# T02_noclock_rev3.net
KiCad netlist of a schematic drawn in EAGLE
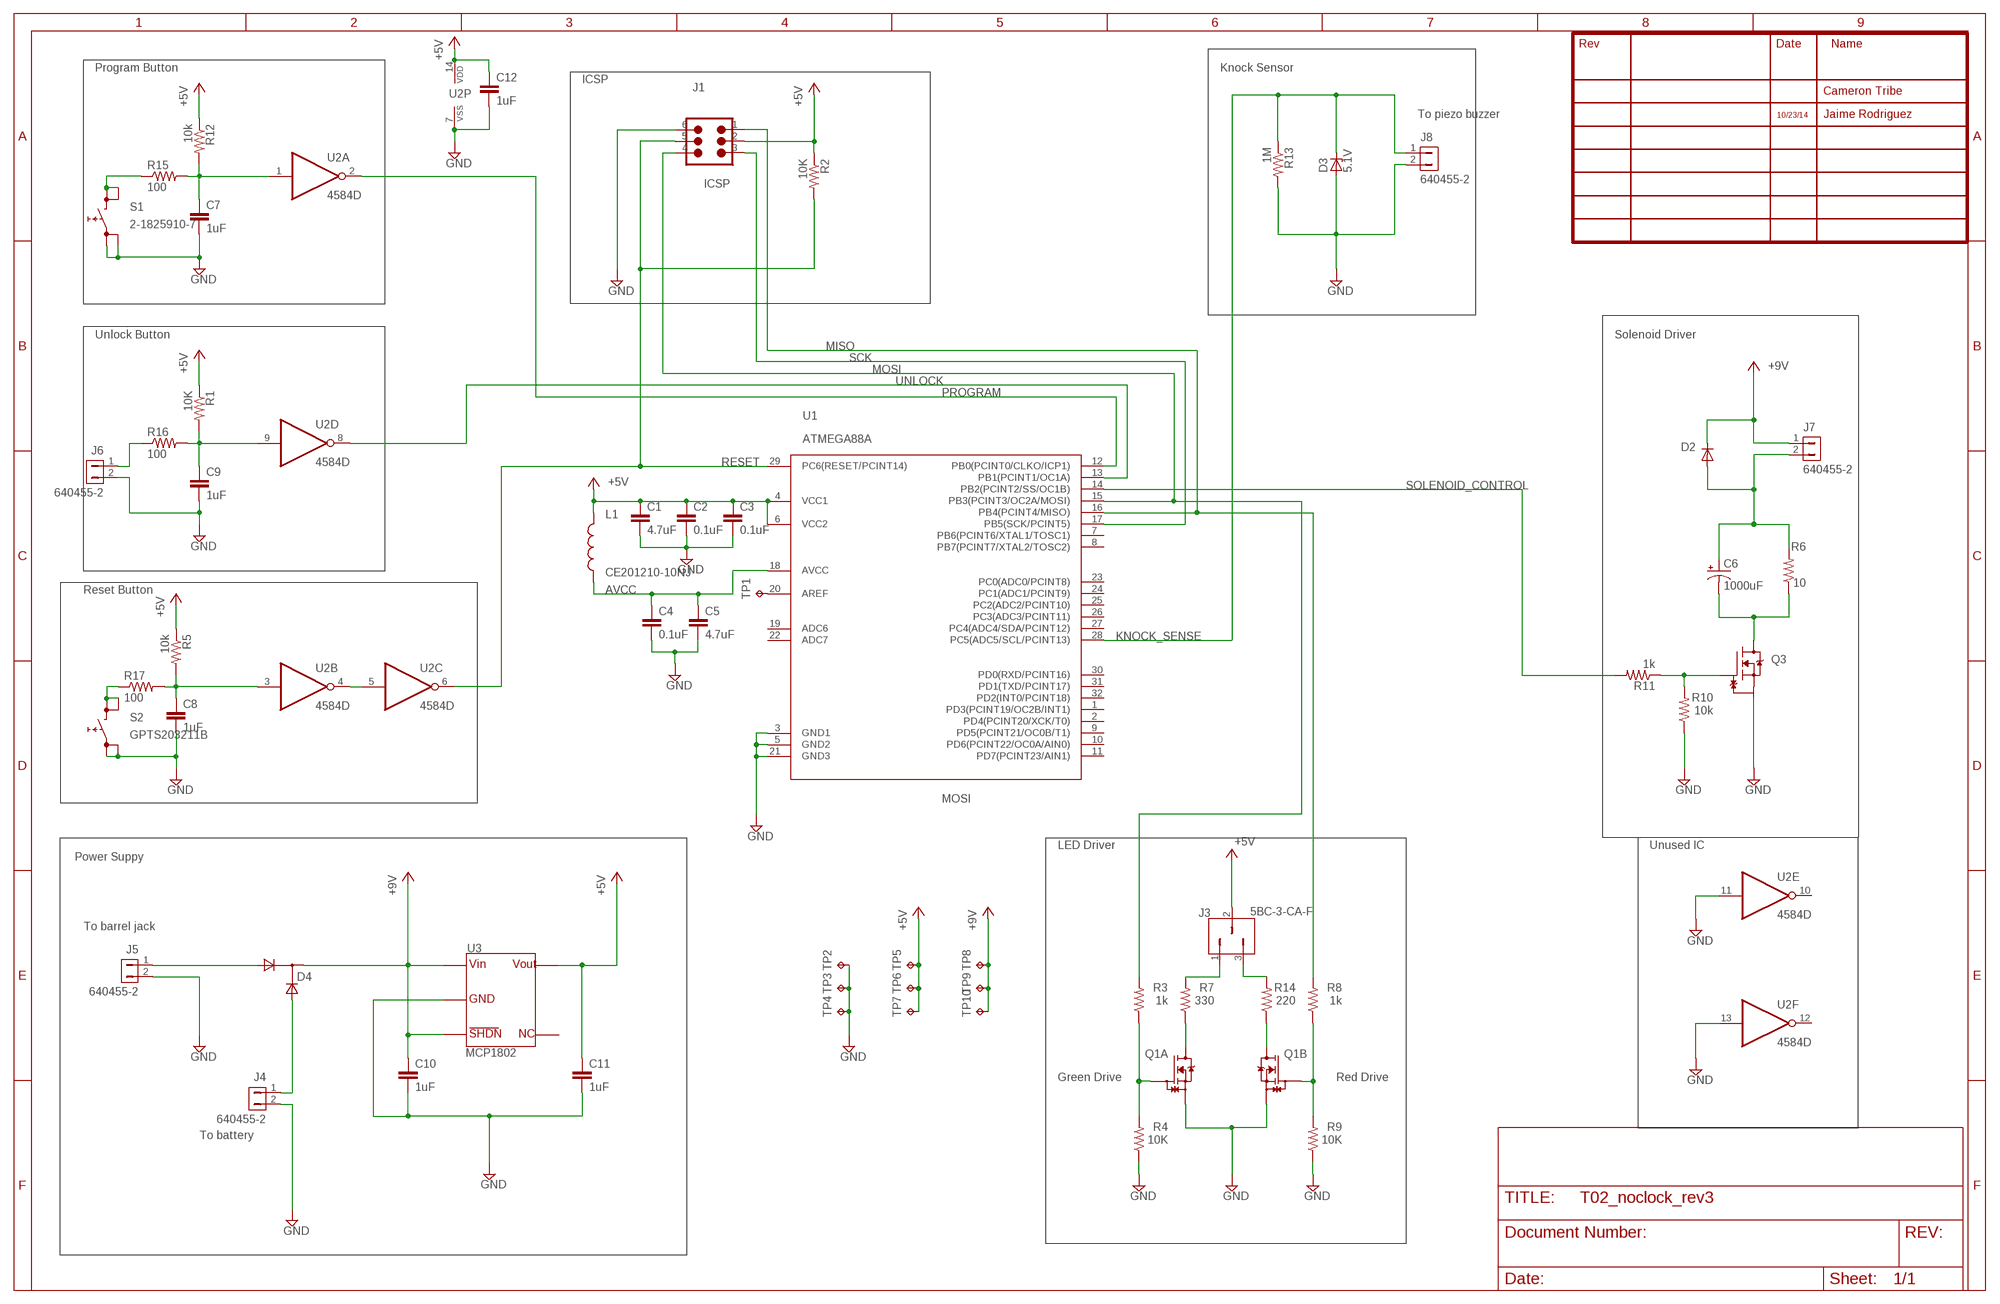
[diagram p0: schematic, sheet 1]

(export (version "E")
  (design (tool "Eeschema 10.0.6"))
  (components
    (comp (ref "C1")
      (value "4.7uF")
      (footprint "eagle-import:C0805")
      (fields (field (name "PARTNUM") "CL21A475KOFNNNE"))
      (libsource (lib "eagle-import") (part "C-EUC0805"))
    )
    (comp (ref "C2")
      (value "0.1uF")
      (footprint "eagle-import:C0805")
      (fields (field (name "PARTNUM") "GRM155R61A104KA01D"))
      (libsource (lib "eagle-import") (part "C-EUC0805"))
    )
    (comp (ref "C3")
      (value "0.1uF")
      (footprint "eagle-import:C0805")
      (fields (field (name "PARTNUM") "GRM155R61A104KA01D"))
      (libsource (lib "eagle-import") (part "C-EUC0805"))
    )
    (comp (ref "C4")
      (value "0.1uF")
      (footprint "eagle-import:C0805")
      (fields (field (name "PARTNUM") "GRM155R61A104KA01D"))
      (libsource (lib "eagle-import") (part "C-EUC0805"))
    )
    (comp (ref "C5")
      (value "4.7uF")
      (footprint "eagle-import:C0805")
      (fields (field (name "PARTNUM") "CL21A475KOFNNNE"))
      (libsource (lib "eagle-import") (part "C-EUC0805"))
    )
    (comp (ref "C6")
      (value "1000uF")
      (footprint "eagle-import:EKY-100ELL102MH20D")
      (libsource (lib "eagle-import") (part "EKY-100ELL102MH20D"))
    )
    (comp (ref "C7")
      (value "1uF")
      (footprint "eagle-import:C0805")
      (fields (field (name "PARTNUM") "CL21B105KBFNNNE"))
      (libsource (lib "eagle-import") (part "C-EUC0805"))
    )
    (comp (ref "C8")
      (value "1uF")
      (footprint "eagle-import:C0805")
      (fields (field (name "PARTNUM") "CL21B105KBFNNNE"))
      (libsource (lib "eagle-import") (part "C-EUC0805"))
    )
    (comp (ref "C9")
      (value "1uF")
      (footprint "eagle-import:C0805")
      (fields (field (name "PARTNUM") "CL21B105KBFNNNE"))
      (libsource (lib "eagle-import") (part "C-EUC0805"))
    )
    (comp (ref "C10")
      (value "1uF")
      (footprint "eagle-import:C0805")
      (fields (field (name "PARTNUM") "CL21B105KBFNNNE"))
      (libsource (lib "eagle-import") (part "C-EUC0805"))
    )
    (comp (ref "C11")
      (value "1uF")
      (footprint "eagle-import:C0805")
      (fields (field (name "PARTNUM") "CL21B105KBFNNNE"))
      (libsource (lib "eagle-import") (part "C-EUC0805"))
    )
    (comp (ref "C12")
      (value "1uF")
      (footprint "eagle-import:C0805")
      (fields (field (name "PARTNUM") "CL21B105KBFNNNE"))
      (libsource (lib "eagle-import") (part "C-EUC0805"))
    )
    (comp (ref "D2")
      (value "GF1")
      (footprint "eagle-import:SMA-DO214AC")
      (fields (field (name "PARTNUM") "S1J"))
      (libsource (lib "eagle-import") (part "GF1"))
    )
    (comp (ref "D3")
      (value "5.1V")
      (footprint "eagle-import:SOT23")
      (fields (field (name "PARTNUM") "BZX84C4V7-TP "))
      (libsource (lib "eagle-import") (part "ZENER-DIODESOT23"))
    )
    (comp (ref "D4")
      (value "PMEG2005CT,215")
      (footprint "eagle-import:SOT-23")
      (libsource (lib "eagle-import") (part "PMEG2005CT,215"))
    )
    (comp (ref "J1")
      (value "ICSP")
      (footprint "eagle-import:ICSP")
      (libsource (lib "eagle-import") (part "ICSP"))
    )
    (comp (ref "J3")
      (value "5BC-3-CA-F")
      (footprint "eagle-import:3_PIN_CONNECTOR")
      (libsource (lib "eagle-import") (part "5BC-3-CA-F"))
    )
    (comp (ref "J4")
      (value "640455-2")
      (footprint "eagle-import:2-PIN_CONNECTOR")
      (libsource (lib "eagle-import") (part "640455-2"))
    )
    (comp (ref "J5")
      (value "640455-2")
      (footprint "eagle-import:2-PIN_CONNECTOR")
      (libsource (lib "eagle-import") (part "640455-2"))
    )
    (comp (ref "J6")
      (value "640455-2")
      (footprint "eagle-import:2-PIN_CONNECTOR")
      (libsource (lib "eagle-import") (part "640455-2"))
    )
    (comp (ref "J7")
      (value "640455-2")
      (footprint "eagle-import:2-PIN_CONNECTOR")
      (libsource (lib "eagle-import") (part "640455-2"))
    )
    (comp (ref "J8")
      (value "640455-2")
      (footprint "eagle-import:2-PIN_CONNECTOR")
      (libsource (lib "eagle-import") (part "640455-2"))
    )
    (comp (ref "L1")
      (value "CE201210-10NJ")
      (footprint "eagle-import:R0805")
      (libsource (lib "eagle-import") (part "CE201210-10NJ"))
    )
    (comp (ref "Q1")
      (value "DMN63D8LDW-7")
      (footprint "eagle-import:SOT363")
      (fields (field (name "PARTNUM") "DMN63D8LDW-7"))
      (libsource (lib "eagle-import") (part "DMN63D8LDW-7"))
    )
    (comp (ref "Q3")
      (value "DMG1012UW-7")
      (footprint "eagle-import:SOT323")
      (libsource (lib "eagle-import") (part "DMG1012UW-7"))
    )
    (comp (ref "R1")
      (value "10K")
      (footprint "eagle-import:R0805")
      (fields (field (name "PARTNUM") "ESR10EZPJ103"))
      (libsource (lib "eagle-import") (part "R-US_R0805"))
    )
    (comp (ref "R2")
      (value "10K")
      (footprint "eagle-import:R0805")
      (fields (field (name "PARTNUM") "ESR10EZPJ103"))
      (libsource (lib "eagle-import") (part "R-US_R0805"))
    )
    (comp (ref "R3")
      (value "1k")
      (footprint "eagle-import:R0805")
      (fields (field (name "PARTNUM") "MCR10ERTF1001"))
      (libsource (lib "eagle-import") (part "R-US_R0805"))
    )
    (comp (ref "R4")
      (value "10K")
      (footprint "eagle-import:R0805")
      (fields (field (name "PARTNUM") "ESR10EZPJ103"))
      (libsource (lib "eagle-import") (part "R-US_R0805"))
    )
    (comp (ref "R5")
      (value "10k")
      (footprint "eagle-import:R0805")
      (fields (field (name "PARTNUM") "ESR10EZPJ103"))
      (libsource (lib "eagle-import") (part "R-US_R0805"))
    )
    (comp (ref "R6")
      (value "10")
      (footprint "eagle-import:R2512")
      (fields (field (name "PARTNUM") "CRM2512-JW-100ELF "))
      (libsource (lib "eagle-import") (part "R-US_R2512"))
    )
    (comp (ref "R7")
      (value "330")
      (footprint "eagle-import:R0805")
      (fields (field (name "PARTNUM") "MCR10ERTF3300"))
      (libsource (lib "eagle-import") (part "R-US_R0805"))
    )
    (comp (ref "R8")
      (value "1k")
      (footprint "eagle-import:R0805")
      (fields (field (name "PARTNUM") "MCR10ERTF1001"))
      (libsource (lib "eagle-import") (part "R-US_R0805"))
    )
    (comp (ref "R9")
      (value "10K")
      (footprint "eagle-import:R0805")
      (fields (field (name "PARTNUM") "ESR10EZPJ103"))
      (libsource (lib "eagle-import") (part "R-US_R0805"))
    )
    (comp (ref "R10")
      (value "10k")
      (footprint "eagle-import:R0805")
      (fields (field (name "PARTNUM") "ESR10EZPJ103"))
      (libsource (lib "eagle-import") (part "R-US_R0805"))
    )
    (comp (ref "R11")
      (value "1k")
      (footprint "eagle-import:R0805")
      (fields (field (name "PARTNUM") "MCR10ERTF1001"))
      (libsource (lib "eagle-import") (part "R-US_R0805"))
    )
    (comp (ref "R12")
      (value "10k")
      (footprint "eagle-import:R0805")
      (fields (field (name "PARTNUM") "ESR10EZPJ103"))
      (libsource (lib "eagle-import") (part "R-US_R0805"))
    )
    (comp (ref "R13")
      (value "1M")
      (footprint "eagle-import:R0805")
      (fields (field (name "PARTNUM") "RMCF0805JT1M00"))
      (libsource (lib "eagle-import") (part "R-US_R0805"))
    )
    (comp (ref "R14")
      (value "220")
      (footprint "eagle-import:R0805")
      (fields (field (name "PARTNUM") "RMCF0805FT220R"))
      (libsource (lib "eagle-import") (part "R-US_R0805"))
    )
    (comp (ref "R15")
      (value "100")
      (footprint "eagle-import:R0805")
      (fields (field (name "PARTNUM") "ESR10EZPJ103"))
      (libsource (lib "eagle-import") (part "R-US_R0805"))
    )
    (comp (ref "R16")
      (value "100")
      (footprint "eagle-import:R0805")
      (fields (field (name "PARTNUM") "ESR10EZPJ103"))
      (libsource (lib "eagle-import") (part "R-US_R0805"))
    )
    (comp (ref "R17")
      (value "100")
      (footprint "eagle-import:R0805")
      (fields (field (name "PARTNUM") "ESR10EZPJ103"))
      (libsource (lib "eagle-import") (part "R-US_R0805"))
    )
    (comp (ref "S1")
      (value "2-1825910-7")
      (footprint "eagle-import:FSM14JH")
      (libsource (lib "eagle-import") (part "2-1825910-7"))
    )
    (comp (ref "S2")
      (value "GPTS203211B")
      (footprint "eagle-import:GPTS203211B")
      (libsource (lib "eagle-import") (part "GPTS203211B"))
    )
    (comp (ref "TP1")
      (value "TPTP19R")
      (footprint "eagle-import:TP19R")
      (libsource (lib "eagle-import") (part "TPTP19R"))
    )
    (comp (ref "TP2")
      (value "TPTP19R")
      (footprint "eagle-import:TP19R")
      (libsource (lib "eagle-import") (part "TPTP19R"))
    )
    (comp (ref "TP3")
      (value "TPTP19R")
      (footprint "eagle-import:TP19R")
      (libsource (lib "eagle-import") (part "TPTP19R"))
    )
    (comp (ref "TP4")
      (value "TPTP19R")
      (footprint "eagle-import:TP19R")
      (libsource (lib "eagle-import") (part "TPTP19R"))
    )
    (comp (ref "TP5")
      (value "TPTP19R")
      (footprint "eagle-import:TP19R")
      (libsource (lib "eagle-import") (part "TPTP19R"))
    )
    (comp (ref "TP6")
      (value "TPTP19R")
      (footprint "eagle-import:TP19R")
      (libsource (lib "eagle-import") (part "TPTP19R"))
    )
    (comp (ref "TP7")
      (value "TPTP19R")
      (footprint "eagle-import:TP19R")
      (libsource (lib "eagle-import") (part "TPTP19R"))
    )
    (comp (ref "TP8")
      (value "TPTP19R")
      (footprint "eagle-import:TP19R")
      (libsource (lib "eagle-import") (part "TPTP19R"))
    )
    (comp (ref "TP9")
      (value "TPTP19R")
      (footprint "eagle-import:TP19R")
      (libsource (lib "eagle-import") (part "TPTP19R"))
    )
    (comp (ref "TP10")
      (value "TPTP19R")
      (footprint "eagle-import:TP19R")
      (libsource (lib "eagle-import") (part "TPTP19R"))
    )
    (comp (ref "U1")
      (value "ATMEGA88A")
      (footprint "eagle-import:TQFP32")
      (fields (field (name "PARTNUM") "ATMEGA88A-AUR "))
      (libsource (lib "eagle-import") (part "ATMEGA88A"))
    )
    (comp (ref "U2")
      (value "4584D")
      (footprint "eagle-import:SO14")
      (fields (field (name "PARTNUM") "4584D"))
      (libsource (lib "eagle-import") (part "4584D"))
    )
    (comp (ref "U3")
      (value "MCP1802")
      (footprint "eagle-import:SOT23-5")
      (libsource (lib "eagle-import") (part "MCP1802"))
    )
  )
  (nets
    (net (code "1") (name "+5V") (class "Default")
      (node (ref "C1") (pin "1") (pinfunction "1_1") (pintype "passive"))
      (node (ref "C11") (pin "1") (pinfunction "1_1") (pintype "passive"))
      (node (ref "C12") (pin "1") (pinfunction "1_1") (pintype "passive"))
      (node (ref "C2") (pin "1") (pinfunction "1_1") (pintype "passive"))
      (node (ref "C3") (pin "1") (pinfunction "1_1") (pintype "passive"))
      (node (ref "J1") (pin "2") (pinfunction "2_2") (pintype "passive"))
      (node (ref "J3") (pin "2") (pinfunction "2_2") (pintype "passive"))
      (node (ref "L1") (pin "2") (pinfunction "2_2") (pintype "passive"))
      (node (ref "R1") (pin "1") (pinfunction "1_1") (pintype "passive"))
      (node (ref "R12") (pin "1") (pinfunction "1_1") (pintype "passive"))
      (node (ref "R2") (pin "1") (pinfunction "1_1") (pintype "passive"))
      (node (ref "R5") (pin "1") (pinfunction "1_1") (pintype "passive"))
      (node (ref "TP5") (pin "TP") (pinfunction "TP_TP") (pintype "input"))
      (node (ref "TP6") (pin "TP") (pinfunction "TP_TP") (pintype "input"))
      (node (ref "TP7") (pin "TP") (pinfunction "TP_TP") (pintype "input"))
      (node (ref "U1") (pin "4") (pinfunction "VCC1_4") (pintype "power_in"))
      (node (ref "U1") (pin "6") (pinfunction "VCC2_6") (pintype "passive"))
      (node (ref "U2") (pin "14") (pinfunction "VDD_14") (pintype "power_in"))
      (node (ref "U3") (pin "5") (pinfunction "VOUT_5") (pintype "passive"))
    )
    (net (code "2") (name "+9V") (class "Default")
      (node (ref "C10") (pin "1") (pinfunction "1_1") (pintype "passive"))
      (node (ref "D2") (pin "K") (pinfunction "C_K") (pintype "passive"))
      (node (ref "D4") (pin "2") (pinfunction "C_2") (pintype "passive"))
      (node (ref "J7") (pin "1") (pinfunction "1_1") (pintype "passive"))
      (node (ref "TP10") (pin "TP") (pinfunction "TP_TP") (pintype "input"))
      (node (ref "TP8") (pin "TP") (pinfunction "TP_TP") (pintype "input"))
      (node (ref "TP9") (pin "TP") (pinfunction "TP_TP") (pintype "input"))
      (node (ref "U3") (pin "1") (pinfunction "VIN_1") (pintype "passive"))
      (node (ref "U3") (pin "3") (pinfunction "SHDN_3") (pintype "passive"))
    )
    (net (code "3") (name "/AVCC") (class "Default")
      (node (ref "C4") (pin "1") (pinfunction "1_1") (pintype "passive"))
      (node (ref "C5") (pin "1") (pinfunction "1_1") (pintype "passive"))
      (node (ref "L1") (pin "1") (pinfunction "1_1") (pintype "passive"))
      (node (ref "U1") (pin "18") (pinfunction "AVCC_18") (pintype "power_in"))
    )
    (net (code "4") (name "/KNOCK_SENSE") (class "Default")
      (node (ref "D3") (pin "3") (pinfunction "C_3") (pintype "passive"))
      (node (ref "J8") (pin "1") (pinfunction "1_1") (pintype "passive"))
      (node (ref "R13") (pin "1") (pinfunction "1_1") (pintype "passive"))
      (node (ref "U1") (pin "28") (pinfunction "PC5(ADC5/SCL/PCINT13)_28") (pintype "bidirectional"))
    )
    (net (code "5") (name "/MISO") (class "Default")
      (node (ref "J1") (pin "1") (pinfunction "1_1") (pintype "passive"))
      (node (ref "R8") (pin "2") (pinfunction "2_2") (pintype "passive"))
      (node (ref "U1") (pin "16") (pinfunction "PB4(PCINT4/MISO)_16") (pintype "bidirectional"))
    )
    (net (code "6") (name "/MOSI") (class "Default")
      (node (ref "J1") (pin "4") (pinfunction "4_4") (pintype "passive"))
      (node (ref "R3") (pin "2") (pinfunction "2_2") (pintype "passive"))
      (node (ref "U1") (pin "15") (pinfunction "PB3(PCINT3/OC2A/MOSI)_15") (pintype "bidirectional"))
    )
    (net (code "7") (name "/PROGRAM") (class "Default")
      (node (ref "U1") (pin "12") (pinfunction "PB0(PCINT0/CLKO/ICP1)_12") (pintype "bidirectional"))
      (node (ref "U2") (pin "2") (pinfunction "O_2") (pintype "output"))
    )
    (net (code "8") (name "/RESET") (class "Default")
      (node (ref "J1") (pin "5") (pinfunction "5_5") (pintype "passive"))
      (node (ref "R2") (pin "2") (pinfunction "2_2") (pintype "passive"))
      (node (ref "U1") (pin "29") (pinfunction "PC6(RESET/PCINT14)_29") (pintype "bidirectional"))
      (node (ref "U2") (pin "6") (pinfunction "O_6") (pintype "output"))
    )
    (net (code "9") (name "/SCK") (class "Default")
      (node (ref "J1") (pin "3") (pinfunction "3_3") (pintype "passive"))
      (node (ref "U1") (pin "17") (pinfunction "PB5(SCK/PCINT5)_17") (pintype "bidirectional"))
    )
    (net (code "10") (name "/SOLENOID_CONTROL") (class "Default")
      (node (ref "R11") (pin "2") (pinfunction "2_2") (pintype "passive"))
      (node (ref "U1") (pin "14") (pinfunction "PB2(PCINT2/SS/OC1B)_14") (pintype "bidirectional"))
    )
    (net (code "11") (name "/UNLOCK") (class "Default")
      (node (ref "U1") (pin "13") (pinfunction "PB1(PCINT1/OC1A)_13") (pintype "bidirectional"))
      (node (ref "U2") (pin "8") (pinfunction "O_8") (pintype "output"))
    )
    (net (code "12") (name "GND") (class "Default")
      (node (ref "C1") (pin "2") (pinfunction "2_2") (pintype "passive"))
      (node (ref "C10") (pin "2") (pinfunction "2_2") (pintype "passive"))
      (node (ref "C11") (pin "2") (pinfunction "2_2") (pintype "passive"))
      (node (ref "C12") (pin "2") (pinfunction "2_2") (pintype "passive"))
      (node (ref "C2") (pin "2") (pinfunction "2_2") (pintype "passive"))
      (node (ref "C3") (pin "2") (pinfunction "2_2") (pintype "passive"))
      (node (ref "C4") (pin "2") (pinfunction "2_2") (pintype "passive"))
      (node (ref "C5") (pin "2") (pinfunction "2_2") (pintype "passive"))
      (node (ref "C7") (pin "2") (pinfunction "2_2") (pintype "passive"))
      (node (ref "C8") (pin "2") (pinfunction "2_2") (pintype "passive"))
      (node (ref "C9") (pin "2") (pinfunction "2_2") (pintype "passive"))
      (node (ref "D3") (pin "1") (pinfunction "A_1") (pintype "passive"))
      (node (ref "J1") (pin "6") (pinfunction "6_6") (pintype "passive"))
      (node (ref "J4") (pin "2") (pinfunction "2_2") (pintype "passive"))
      (node (ref "J5") (pin "2") (pinfunction "2_2") (pintype "passive"))
      (node (ref "J6") (pin "2") (pinfunction "2_2") (pintype "passive"))
      (node (ref "J8") (pin "2") (pinfunction "2_2") (pintype "passive"))
      (node (ref "Q1") (pin "S1") (pinfunction "S_S1") (pintype "passive"))
      (node (ref "Q1") (pin "S2") (pinfunction "S_S2") (pintype "passive"))
      (node (ref "Q3") (pin "3") (pinfunction "S_3") (pintype "passive"))
      (node (ref "R10") (pin "1") (pinfunction "1_1") (pintype "passive"))
      (node (ref "R13") (pin "2") (pinfunction "2_2") (pintype "passive"))
      (node (ref "R4") (pin "1") (pinfunction "1_1") (pintype "passive"))
      (node (ref "R9") (pin "1") (pinfunction "1_1") (pintype "passive"))
      (node (ref "S1") (pin "1") (pinfunction "1_1") (pintype "passive"))
      (node (ref "S1") (pin "2") (pinfunction "2_2") (pintype "passive"))
      (node (ref "S2") (pin "1") (pinfunction "1_1") (pintype "passive"))
      (node (ref "S2") (pin "2") (pinfunction "2_2") (pintype "passive"))
      (node (ref "TP2") (pin "TP") (pinfunction "TP_TP") (pintype "input"))
      (node (ref "TP3") (pin "TP") (pinfunction "TP_TP") (pintype "input"))
      (node (ref "TP4") (pin "TP") (pinfunction "TP_TP") (pintype "input"))
      (node (ref "U1") (pin "21") (pinfunction "GND3_21") (pintype "power_in"))
      (node (ref "U1") (pin "3") (pinfunction "GND1_3") (pintype "power_in"))
      (node (ref "U1") (pin "5") (pinfunction "GND2_5") (pintype "power_in"))
      (node (ref "U2") (pin "11") (pinfunction "I_11") (pintype "input"))
      (node (ref "U2") (pin "13") (pinfunction "I_13") (pintype "input"))
      (node (ref "U2") (pin "7") (pinfunction "VSS_7") (pintype "power_in"))
      (node (ref "U3") (pin "2") (pinfunction "GND_2") (pintype "power_in"))
    )
    (net (code "13") (name "Net-(C6-Pad+)") (class "Default")
      (node (ref "C6") (pin "+") (pinfunction "+_+") (pintype "passive"))
      (node (ref "D2") (pin "A") (pinfunction "A_A") (pintype "passive"))
      (node (ref "J7") (pin "2") (pinfunction "2_2") (pintype "passive"))
      (node (ref "R6") (pin "2") (pinfunction "2_2") (pintype "passive"))
    )
    (net (code "14") (name "Net-(D4-A1)") (class "Default")
      (node (ref "D4") (pin "3") (pinfunction "A1_3") (pintype "passive"))
      (node (ref "J5") (pin "1") (pinfunction "1_1") (pintype "passive"))
    )
    (net (code "15") (name "Net-(D4-A2)") (class "Default")
      (node (ref "D4") (pin "1") (pinfunction "A2_1") (pintype "passive"))
      (node (ref "J4") (pin "1") (pinfunction "1_1") (pintype "passive"))
    )
    (net (code "16") (name "Net-(J3-Pad1)") (class "Default")
      (node (ref "J3") (pin "1") (pinfunction "1_1") (pintype "passive"))
      (node (ref "R7") (pin "2") (pinfunction "2_2") (pintype "passive"))
    )
    (net (code "17") (name "Net-(J3-Pad3)") (class "Default")
      (node (ref "J3") (pin "3") (pinfunction "3_3") (pintype "passive"))
      (node (ref "R14") (pin "2") (pinfunction "2_2") (pintype "passive"))
    )
    (net (code "18") (name "Net-(J6-Pad1)") (class "Default")
      (node (ref "J6") (pin "1") (pinfunction "1_1") (pintype "passive"))
      (node (ref "R16") (pin "1") (pinfunction "1_1") (pintype "passive"))
    )
    (net (code "19") (name "Net-(Q1A-D)") (class "Default")
      (node (ref "Q1") (pin "D1") (pinfunction "D_D1") (pintype "passive"))
      (node (ref "R7") (pin "1") (pinfunction "1_1") (pintype "passive"))
    )
    (net (code "20") (name "Net-(Q1A-G)") (class "Default")
      (node (ref "Q1") (pin "G1") (pinfunction "G_G1") (pintype "passive"))
      (node (ref "R3") (pin "1") (pinfunction "1_1") (pintype "passive"))
      (node (ref "R4") (pin "2") (pinfunction "2_2") (pintype "passive"))
    )
    (net (code "21") (name "Net-(Q1B-D)") (class "Default")
      (node (ref "Q1") (pin "D2") (pinfunction "D_D2") (pintype "passive"))
      (node (ref "R14") (pin "1") (pinfunction "1_1") (pintype "passive"))
    )
    (net (code "22") (name "Net-(Q1B-G)") (class "Default")
      (node (ref "Q1") (pin "G2") (pinfunction "G_G2") (pintype "passive"))
      (node (ref "R8") (pin "1") (pinfunction "1_1") (pintype "passive"))
      (node (ref "R9") (pin "2") (pinfunction "2_2") (pintype "passive"))
    )
    (net (code "23") (name "Net-(Q3-D)") (class "Default")
      (node (ref "C6") (pin "-") (pinfunction "-_-") (pintype "passive"))
      (node (ref "Q3") (pin "1") (pinfunction "D_1") (pintype "passive"))
      (node (ref "R6") (pin "1") (pinfunction "1_1") (pintype "passive"))
    )
    (net (code "24") (name "Net-(Q3-G)") (class "Default")
      (node (ref "Q3") (pin "2") (pinfunction "G_2") (pintype "passive"))
      (node (ref "R10") (pin "2") (pinfunction "2_2") (pintype "passive"))
      (node (ref "R11") (pin "1") (pinfunction "1_1") (pintype "passive"))
    )
    (net (code "25") (name "Net-(R15-Pad1)") (class "Default")
      (node (ref "R15") (pin "1") (pinfunction "1_1") (pintype "passive"))
      (node (ref "S1") (pin "3") (pinfunction "3_3") (pintype "passive"))
      (node (ref "S1") (pin "4") (pinfunction "4_4") (pintype "passive"))
    )
    (net (code "26") (name "Net-(R17-Pad1)") (class "Default")
      (node (ref "R17") (pin "1") (pinfunction "1_1") (pintype "passive"))
      (node (ref "S2") (pin "3") (pinfunction "3_3") (pintype "passive"))
      (node (ref "S2") (pin "4") (pinfunction "4_4") (pintype "passive"))
    )
    (net (code "27") (name "Net-(U1-AREF)") (class "Default")
      (node (ref "TP1") (pin "TP") (pinfunction "TP_TP") (pintype "input"))
      (node (ref "U1") (pin "20") (pinfunction "AREF_20") (pintype "power_in"))
    )
    (net (code "28") (name "Net-(U2A-I)") (class "Default")
      (node (ref "C7") (pin "1") (pinfunction "1_1") (pintype "passive"))
      (node (ref "R12") (pin "2") (pinfunction "2_2") (pintype "passive"))
      (node (ref "R15") (pin "2") (pinfunction "2_2") (pintype "passive"))
      (node (ref "U2") (pin "1") (pinfunction "I_1") (pintype "input"))
    )
    (net (code "29") (name "Net-(U2B-I)") (class "Default")
      (node (ref "C8") (pin "1") (pinfunction "1_1") (pintype "passive"))
      (node (ref "R17") (pin "2") (pinfunction "2_2") (pintype "passive"))
      (node (ref "R5") (pin "2") (pinfunction "2_2") (pintype "passive"))
      (node (ref "U2") (pin "3") (pinfunction "I_3") (pintype "input"))
    )
    (net (code "30") (name "Net-(U2B-O)") (class "Default")
      (node (ref "U2") (pin "4") (pinfunction "O_4") (pintype "output"))
      (node (ref "U2") (pin "5") (pinfunction "I_5") (pintype "input"))
    )
    (net (code "31") (name "Net-(U2D-I)") (class "Default")
      (node (ref "C9") (pin "1") (pinfunction "1_1") (pintype "passive"))
      (node (ref "R1") (pin "2") (pinfunction "2_2") (pintype "passive"))
      (node (ref "R16") (pin "2") (pinfunction "2_2") (pintype "passive"))
      (node (ref "U2") (pin "9") (pinfunction "I_9") (pintype "input"))
    )
    (net (code "32") (name "unconnected-(U1-ADC6-Pad19)") (class "Default")
      (node (ref "U1") (pin "19") (pinfunction "ADC6_19") (pintype "bidirectional"))
    )
    (net (code "33") (name "unconnected-(U1-ADC7-Pad22)") (class "Default")
      (node (ref "U1") (pin "22") (pinfunction "ADC7_22") (pintype "bidirectional"))
    )
    (net (code "34") (name "unconnected-(U1-PB6(PCINT6{slash}XTAL1{slash}TOSC1)-Pad7)") (class "Default")
      (node (ref "U1") (pin "7") (pinfunction "PB6(PCINT6/XTAL1/TOSC1)_7") (pintype "bidirectional"))
    )
    (net (code "35") (name "unconnected-(U1-PB7(PCINT7{slash}XTAL2{slash}TOSC2)-Pad8)") (class "Default")
      (node (ref "U1") (pin "8") (pinfunction "PB7(PCINT7/XTAL2/TOSC2)_8") (pintype "bidirectional"))
    )
    (net (code "36") (name "unconnected-(U1-PC0(ADC0{slash}PCINT8)-Pad23)") (class "Default")
      (node (ref "U1") (pin "23") (pinfunction "PC0(ADC0/PCINT8)_23") (pintype "bidirectional"))
    )
    (net (code "37") (name "unconnected-(U1-PC1(ADC1{slash}PCINT9)-Pad24)") (class "Default")
      (node (ref "U1") (pin "24") (pinfunction "PC1(ADC1/PCINT9)_24") (pintype "bidirectional"))
    )
    (net (code "38") (name "unconnected-(U1-PC2(ADC2{slash}PCINT10)-Pad25)") (class "Default")
      (node (ref "U1") (pin "25") (pinfunction "PC2(ADC2/PCINT10)_25") (pintype "bidirectional"))
    )
    (net (code "39") (name "unconnected-(U1-PC3(ADC3{slash}PCINT11)-Pad26)") (class "Default")
      (node (ref "U1") (pin "26") (pinfunction "PC3(ADC3/PCINT11)_26") (pintype "bidirectional"))
    )
    (net (code "40") (name "unconnected-(U1-PC4(ADC4{slash}SDA{slash}PCINT12)-Pad27)") (class "Default")
      (node (ref "U1") (pin "27") (pinfunction "PC4(ADC4/SDA/PCINT12)_27") (pintype "bidirectional"))
    )
    (net (code "41") (name "unconnected-(U1-PD0(RXD{slash}PCINT16)-Pad30)") (class "Default")
      (node (ref "U1") (pin "30") (pinfunction "PD0(RXD/PCINT16)_30") (pintype "bidirectional"))
    )
    (net (code "42") (name "unconnected-(U1-PD1(TXD{slash}PCINT17)-Pad31)") (class "Default")
      (node (ref "U1") (pin "31") (pinfunction "PD1(TXD/PCINT17)_31") (pintype "bidirectional"))
    )
    (net (code "43") (name "unconnected-(U1-PD2(INT0{slash}PCINT18)-Pad32)") (class "Default")
      (node (ref "U1") (pin "32") (pinfunction "PD2(INT0/PCINT18)_32") (pintype "bidirectional"))
    )
    (net (code "44") (name "unconnected-(U1-PD3(PCINT19{slash}OC2B{slash}INT1)-Pad1)") (class "Default")
      (node (ref "U1") (pin "1") (pinfunction "PD3(PCINT19/OC2B/INT1)_1") (pintype "bidirectional"))
    )
    (net (code "45") (name "unconnected-(U1-PD4(PCINT20{slash}XCK{slash}T0)-Pad2)") (class "Default")
      (node (ref "U1") (pin "2") (pinfunction "PD4(PCINT20/XCK/T0)_2") (pintype "bidirectional"))
    )
    (net (code "46") (name "unconnected-(U1-PD5(PCINT21{slash}OC0B{slash}T1)-Pad9)") (class "Default")
      (node (ref "U1") (pin "9") (pinfunction "PD5(PCINT21/OC0B/T1)_9") (pintype "bidirectional"))
    )
    (net (code "47") (name "unconnected-(U1-PD6(PCINT22{slash}OC0A{slash}AIN0)-Pad10)") (class "Default")
      (node (ref "U1") (pin "10") (pinfunction "PD6(PCINT22/OC0A/AIN0)_10") (pintype "bidirectional"))
    )
    (net (code "48") (name "unconnected-(U1-PD7(PCINT23{slash}AIN1)-Pad11)") (class "Default")
      (node (ref "U1") (pin "11") (pinfunction "PD7(PCINT23/AIN1)_11") (pintype "bidirectional"))
    )
    (net (code "49") (name "unconnected-(U2E-O-Pad10)") (class "Default")
      (node (ref "U2") (pin "10") (pinfunction "O_10") (pintype "output"))
    )
    (net (code "50") (name "unconnected-(U2F-O-Pad12)") (class "Default")
      (node (ref "U2") (pin "12") (pinfunction "O_12") (pintype "output"))
    )
    (net (code "51") (name "unconnected-(U3-NC-Pad4)") (class "Default")
      (node (ref "U3") (pin "4") (pinfunction "NC_4") (pintype "no_connect"))
    )
  )
)
